# ethernet.net
KiCad netlist of a schematic drawn in Altium Designer
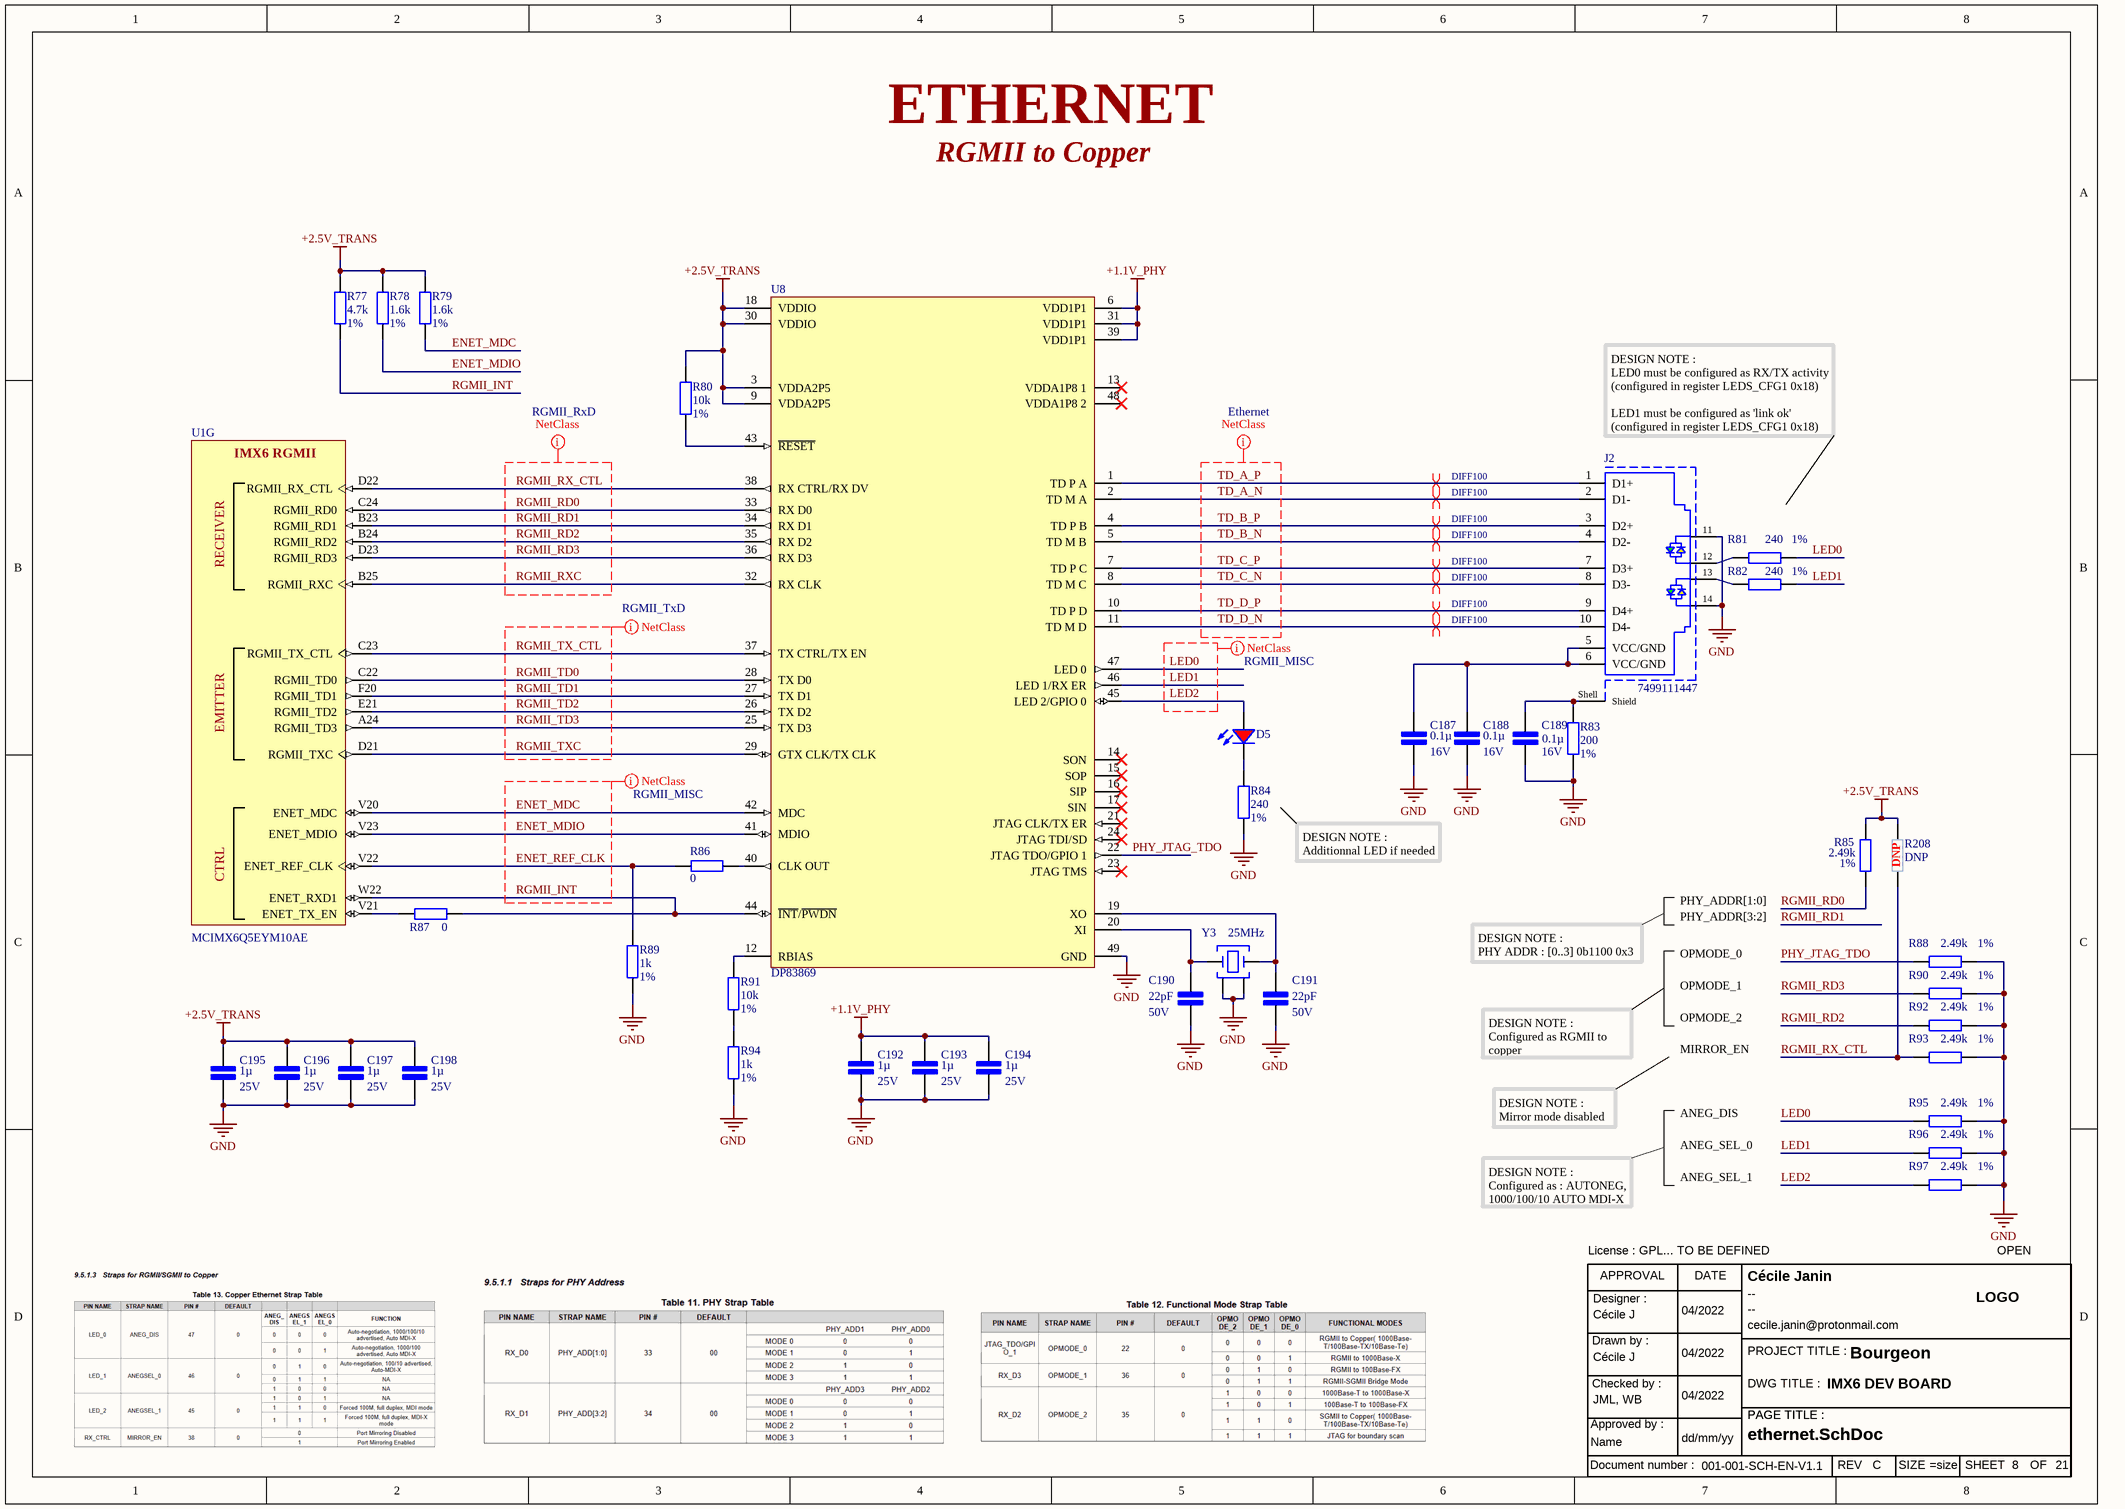
[diagram p0: ethernet.SchDoc]

(export (version "E")
  (design (tool "Eeschema 10.0.6"))
  (components
    (comp (ref "C187")
      (value "0.1µ")
      (footprint "Cap cer 0402/1005")
      (description "cap solid electrolyte 0.1µ 6.3V 10%")
      (fields (field (name "TENSION DU DIÉLECTRIQUE") "16V"))
      (libsource (lib "First Board IMX6") (part "cap 0.1µ 16V"))
    )
    (comp (ref "C188")
      (value "0.1µ")
      (footprint "Cap cer 0402/1005")
      (description "cap solid electrolyte 0.1µ 6.3V 10%")
      (fields (field (name "TENSION DU DIÉLECTRIQUE") "16V"))
      (libsource (lib "First Board IMX6") (part "cap 0.1µ 16V"))
    )
    (comp (ref "C189")
      (value "0.1µ")
      (footprint "Cap cer 0402/1005")
      (description "cap solid electrolyte 0.1µ 6.3V 10%")
      (fields (field (name "TENSION DU DIÉLECTRIQUE") "16V"))
      (libsource (lib "") (part "cap 0.1µ 16V_1"))
    )
    (comp (ref "C190")
      (value "22pF")
      (footprint "Cap cer 0402/1005")
      (description "cap cer 22pF 50V 5% NP0 0402")
      (fields (field (name "TENSION DU DIÉLECTRIQUE") "50V"))
      (libsource (lib "First Board IMX6") (part "cap 22pF 50V"))
    )
    (comp (ref "C191")
      (value "22pF")
      (footprint "Cap cer 0402/1005")
      (description "cap cer 22pF 50V 5% NP0 0402")
      (fields (field (name "TENSION DU DIÉLECTRIQUE") "50V"))
      (libsource (lib "First Board IMX6") (part "cap 22pF 50V"))
    )
    (comp (ref "C192")
      (value "1µ")
      (footprint "Cap cer 0402/1005")
      (description "cap cer 1µ 25V 10% X5R 0402")
      (fields (field (name "TENSION DU DIÉLECTRIQUE") "25V"))
      (libsource (lib "First Board IMX6") (part "cap 1µ 25V"))
    )
    (comp (ref "C193")
      (value "1µ")
      (footprint "Cap cer 0402/1005")
      (description "cap cer 1µ 25V 10% X5R 0402")
      (fields (field (name "TENSION DU DIÉLECTRIQUE") "25V"))
      (libsource (lib "First Board IMX6") (part "cap 1µ 25V"))
    )
    (comp (ref "C194")
      (value "1µ")
      (footprint "Cap cer 0402/1005")
      (description "cap cer 1µ 25V 10% X5R 0402")
      (fields (field (name "TENSION DU DIÉLECTRIQUE") "25V"))
      (libsource (lib "First Board IMX6") (part "cap 1µ 25V"))
    )
    (comp (ref "C195")
      (value "1µ")
      (footprint "Cap cer 0402/1005")
      (description "cap cer 1µ 25V 10% X5R 0402")
      (fields (field (name "TENSION DU DIÉLECTRIQUE") "25V"))
      (libsource (lib "First Board IMX6") (part "cap 1µ 25V"))
    )
    (comp (ref "C196")
      (value "1µ")
      (footprint "Cap cer 0402/1005")
      (description "cap cer 1µ 25V 10% X5R 0402")
      (fields (field (name "TENSION DU DIÉLECTRIQUE") "25V"))
      (libsource (lib "First Board IMX6") (part "cap 1µ 25V"))
    )
    (comp (ref "C197")
      (value "1µ")
      (footprint "Cap cer 0402/1005")
      (description "cap cer 1µ 25V 10% X5R 0402")
      (fields (field (name "TENSION DU DIÉLECTRIQUE") "25V"))
      (libsource (lib "First Board IMX6") (part "cap 1µ 25V"))
    )
    (comp (ref "C198")
      (value "1µ")
      (footprint "Cap cer 0402/1005")
      (description "cap cer 1µ 25V 10% X5R 0402")
      (fields (field (name "TENSION DU DIÉLECTRIQUE") "25V"))
      (libsource (lib "First Board IMX6") (part "cap 1µ 25V"))
    )
    (comp (ref "D5")
      (value "Red, 2V, 120deg")
      (footprint "LED red 0603")
      (description "WL-SMCC SMD Mono-color Chip LED Compact, size 0603, Red, 2V, 120deg 150060RS73220")
      (fields (field (name "PART NUMBER") "150060RS73220") (field (name "PUBLISHER") "Wurth Elektronik"))
      (libsource (lib "First Board IMX6") (part "LED Red 0603"))
    )
    (comp (ref "J2")
      (value "7499111447")
      (footprint "RJ45 7499111447")
      (libsource (lib "First Board IMX6") (part "RJ45 7499111447"))
    )
    (comp (ref "R77")
      (value "4.7k")
      (footprint "Res 0402/1005")
      (description "res 4.7k 1% 0402")
      (fields (field (name "POURCENTAGE") "1%"))
      (libsource (lib "First Board IMX6") (part "res 4.7k 1%"))
    )
    (comp (ref "R78")
      (value "1.6k")
      (footprint "Res 0402/1005")
      (description "res 1.6k 1% 0402")
      (fields (field (name "POURCENTAGE") "1%"))
      (libsource (lib "First Board IMX6") (part "res 1.6k 1%"))
    )
    (comp (ref "R79")
      (value "1.6k")
      (footprint "Res 0402/1005")
      (description "res 1.6k 1% 0402")
      (fields (field (name "POURCENTAGE") "1%"))
      (libsource (lib "First Board IMX6") (part "res 1.6k 1%"))
    )
    (comp (ref "R80")
      (value "10k")
      (footprint "Res 0402/1005")
      (description "res 10k 1% 0402")
      (fields (field (name "POURCENTAGE") "1%"))
      (libsource (lib "First Board IMX6") (part "res 10k 1%"))
    )
    (comp (ref "R81")
      (value "240")
      (footprint "Res 0402/1005")
      (description "res 240 1% 0402")
      (fields (field (name "POURCENTAGE") "1%"))
      (libsource (lib "First Board IMX6") (part "res 240 1%"))
    )
    (comp (ref "R82")
      (value "240")
      (footprint "Res 0402/1005")
      (description "res 240 1% 0402")
      (fields (field (name "POURCENTAGE") "1%"))
      (libsource (lib "First Board IMX6") (part "res 240 1%"))
    )
    (comp (ref "R83")
      (value "200")
      (footprint "Res 0402/1005")
      (description "res 200 1% 0402")
      (fields (field (name "POURCENTAGE") "1%"))
      (libsource (lib "First Board IMX6") (part "res 200 1%"))
    )
    (comp (ref "R84")
      (value "240")
      (footprint "Res 0402/1005")
      (description "res 240 1% 0402")
      (fields (field (name "POURCENTAGE") "1%"))
      (libsource (lib "First Board IMX6") (part "res 240 1%"))
    )
    (comp (ref "R85")
      (value "2.49k")
      (footprint "Res 0402/1005")
      (description "res 2.49k 1% 0402")
      (fields (field (name "POURCENTAGE") "1%"))
      (libsource (lib "First Board IMX6") (part "res 2.49k 1%"))
    )
    (comp (ref "R86")
      (value "0")
      (footprint "Res 0402/1005")
      (description "res 0402")
      (libsource (lib "First Board IMX6") (part "res 0Ohm small"))
    )
    (comp (ref "R87")
      (value "0")
      (footprint "Res 0402/1005")
      (description "res 0402")
      (libsource (lib "First Board IMX6") (part "res 0Ohm small"))
    )
    (comp (ref "R88")
      (value "2.49k")
      (footprint "Res 0402/1005")
      (description "res 2.49k 1% 0402")
      (fields (field (name "POURCENTAGE") "1%"))
      (libsource (lib "First Board IMX6") (part "res 2.49k 1%"))
    )
    (comp (ref "R89")
      (value "1k")
      (footprint "Res 0402/1005")
      (description "res 1k 1% 0402")
      (fields (field (name "POURCENTAGE") "1%"))
      (libsource (lib "First Board IMX6") (part "res 1k 1%"))
    )
    (comp (ref "R90")
      (value "2.49k")
      (footprint "Res 0402/1005")
      (description "res 2.49k 1% 0402")
      (fields (field (name "POURCENTAGE") "1%"))
      (libsource (lib "First Board IMX6") (part "res 2.49k 1%"))
    )
    (comp (ref "R91")
      (value "10k")
      (footprint "Res 0402/1005")
      (description "res 10k 1% 0402")
      (fields (field (name "POURCENTAGE") "1%"))
      (libsource (lib "First Board IMX6") (part "res 10k 1%"))
    )
    (comp (ref "R92")
      (value "2.49k")
      (footprint "Res 0402/1005")
      (description "res 2.49k 1% 0402")
      (fields (field (name "POURCENTAGE") "1%"))
      (libsource (lib "First Board IMX6") (part "res 2.49k 1%"))
    )
    (comp (ref "R93")
      (value "2.49k")
      (footprint "Res 0402/1005")
      (description "res 2.49k 1% 0402")
      (fields (field (name "POURCENTAGE") "1%"))
      (libsource (lib "First Board IMX6") (part "res 2.49k 1%"))
    )
    (comp (ref "R94")
      (value "1k")
      (footprint "Res 0402/1005")
      (description "res 1k 1% 0402")
      (fields (field (name "POURCENTAGE") "1%"))
      (libsource (lib "First Board IMX6") (part "res 1k 1%"))
    )
    (comp (ref "R95")
      (value "2.49k")
      (footprint "Res 0402/1005")
      (description "res 2.49k 1% 0402")
      (fields (field (name "POURCENTAGE") "1%"))
      (libsource (lib "First Board IMX6") (part "res 2.49k 1%"))
    )
    (comp (ref "R96")
      (value "2.49k")
      (footprint "Res 0402/1005")
      (description "res 2.49k 1% 0402")
      (fields (field (name "POURCENTAGE") "1%"))
      (libsource (lib "First Board IMX6") (part "res 2.49k 1%"))
    )
    (comp (ref "R97")
      (value "2.49k")
      (footprint "Res 0402/1005")
      (description "res 2.49k 1% 0402")
      (fields (field (name "POURCENTAGE") "1%"))
      (libsource (lib "First Board IMX6") (part "res 2.49k 1%"))
    )
    (comp (ref "R208")
      (value "DNP")
      (footprint "Res 0402/1005")
      (description "res DNP 0403")
      (libsource (lib "First Board IMX6") (part "res DNP 0402"))
    )
    (comp (ref "TB7")
      (value "Title bloc ANSI modified")
      (libsource (lib "First Board IMX6") (part "Title bloc ANSI"))
    )
    (comp (ref "U1")
      (value "MCIMX6Q5EYM10AE")
      (footprint "FRES-2197-01")
      (fields
        (field (name "PARTNUMBER") "MCIMX6Q5EYM10ACR")
        (field (name "MANUFACTURER") "Freescale Semiconductor")
      )
      (libsource (lib "First Board IMX6") (part "IMX6Q5EYM10AE"))
    )
    (comp (ref "U8")
      (value "DP83869")
      (footprint "QFN48")
      (description "Ethernet transciever")
      (libsource (lib "First Board IMX6") (part "IC DP83869"))
    )
    (comp (ref "Y3")
      (value "25MHz")
      (footprint "IQXC-42")
      (description "WE-XTAL, 25MHz, +/-10ppm")
      (fields
        (field (name "MANUFACTURER PART NUMBER") "830108212509")
        (field (name "MANUFACTURER") "Wurth Elektronik")
      )
      (libsource (lib "First Board IMX6") (part "XTAL 25MHz"))
    )
  )
  (nets
    (net (code "1") (name "+1.1V_PHY") (class "Default")
      (node (ref "C192") (pin "1") (pinfunction "3_1") (pintype "passive"))
      (node (ref "C193") (pin "1") (pinfunction "3_1") (pintype "passive"))
      (node (ref "C194") (pin "1") (pinfunction "3_1") (pintype "passive"))
      (node (ref "U8") (pin "31") (pinfunction "VDD1P1_31") (pintype "power_in"))
      (node (ref "U8") (pin "39") (pinfunction "VDD1P1_39") (pintype "power_in"))
      (node (ref "U8") (pin "6") (pinfunction "VDD1P1_6") (pintype "power_in"))
    )
    (net (code "2") (name "+2.5V_TRANS") (class "Default")
      (node (ref "C195") (pin "1") (pinfunction "3_1") (pintype "passive"))
      (node (ref "C196") (pin "1") (pinfunction "3_1") (pintype "passive"))
      (node (ref "C197") (pin "1") (pinfunction "3_1") (pintype "passive"))
      (node (ref "C198") (pin "1") (pinfunction "3_1") (pintype "passive"))
      (node (ref "R208") (pin "2") (pintype "passive"))
      (node (ref "R77") (pin "2") (pintype "passive"))
      (node (ref "R78") (pin "2") (pintype "passive"))
      (node (ref "R79") (pin "2") (pintype "passive"))
      (node (ref "R80") (pin "2") (pintype "passive"))
      (node (ref "R85") (pin "2") (pintype "passive"))
      (node (ref "U8") (pin "18") (pinfunction "VDDIO_18") (pintype "power_in"))
      (node (ref "U8") (pin "3") (pinfunction "VDDA2P5_3") (pintype "power_in"))
      (node (ref "U8") (pin "30") (pinfunction "VDDIO_30") (pintype "power_in"))
      (node (ref "U8") (pin "9") (pinfunction "VDDA2P5_9") (pintype "power_in"))
    )
    (net (code "3") (name "/ENET_MDC") (class "Default")
      (node (ref "R79") (pin "1") (pintype "passive"))
      (node (ref "U1") (pin "V20") (pinfunction "ENET_MDC_V20") (pintype "bidirectional"))
      (node (ref "U8") (pin "42") (pinfunction "MDC_42") (pintype "input"))
    )
    (net (code "4") (name "/ENET_MDIO") (class "Default")
      (node (ref "R78") (pin "1") (pintype "passive"))
      (node (ref "U1") (pin "V23") (pinfunction "ENET_MDIO_V23") (pintype "bidirectional"))
      (node (ref "U8") (pin "41") (pinfunction "MDIO_41") (pintype "bidirectional"))
    )
    (net (code "5") (name "/ENET_REF_CLK") (class "Default")
      (node (ref "R86") (pin "1") (pintype "passive"))
      (node (ref "R89") (pin "2") (pintype "passive"))
      (node (ref "U1") (pin "V22") (pinfunction "ENET_REF_CLK_V22") (pintype "bidirectional"))
    )
    (net (code "6") (name "/LED0") (class "Default")
      (node (ref "R81") (pin "2") (pintype "passive"))
      (node (ref "R95") (pin "2") (pintype "passive"))
      (node (ref "U8") (pin "47") (pinfunction "LED_0_47") (pintype "output"))
    )
    (net (code "7") (name "/LED1") (class "Default")
      (node (ref "R82") (pin "2") (pintype "passive"))
      (node (ref "R96") (pin "2") (pintype "passive"))
      (node (ref "U8") (pin "46") (pinfunction "LED_1/RX_ER_46") (pintype "output"))
    )
    (net (code "8") (name "/LED2") (class "Default")
      (node (ref "D5") (pin "2") (pinfunction "A_2") (pintype "passive"))
      (node (ref "R97") (pin "2") (pintype "passive"))
      (node (ref "U8") (pin "45") (pinfunction "LED_2/GPIO_0_45") (pintype "bidirectional"))
    )
    (net (code "9") (name "/PHY_JTAG_TDO") (class "Default")
      (node (ref "R88") (pin "2") (pintype "passive"))
      (node (ref "U8") (pin "22") (pinfunction "JTAG_TDO/GPIO_1_22") (pintype "output"))
    )
    (net (code "10") (name "/RGMII_INT") (class "Default")
      (node (ref "R77") (pin "1") (pintype "passive"))
      (node (ref "R87") (pin "2") (pintype "passive"))
      (node (ref "U1") (pin "W22") (pinfunction "ENET_RXD1_W22") (pintype "bidirectional"))
      (node (ref "U8") (pin "44") (pinfunction "~{INT}/~{PWDN}_44") (pintype "bidirectional"))
    )
    (net (code "11") (name "/RGMII_RD0") (class "Default")
      (node (ref "R85") (pin "1") (pintype "passive"))
      (node (ref "U1") (pin "C24") (pinfunction "RGMII_RD0_C24") (pintype "input"))
      (node (ref "U8") (pin "33") (pinfunction "RX_D0_33") (pintype "output"))
    )
    (net (code "12") (name "/RGMII_RD1") (class "Default")
      (node (ref "U1") (pin "B23") (pinfunction "RGMII_RD1_B23") (pintype "input"))
      (node (ref "U8") (pin "34") (pinfunction "RX_D1_34") (pintype "output"))
    )
    (net (code "13") (name "/RGMII_RD2") (class "Default")
      (node (ref "R92") (pin "2") (pintype "passive"))
      (node (ref "U1") (pin "B24") (pinfunction "RGMII_RD2_B24") (pintype "input"))
      (node (ref "U8") (pin "35") (pinfunction "RX_D2_35") (pintype "output"))
    )
    (net (code "14") (name "/RGMII_RD3") (class "Default")
      (node (ref "R90") (pin "2") (pintype "passive"))
      (node (ref "U1") (pin "D23") (pinfunction "RGMII_RD3_D23") (pintype "input"))
      (node (ref "U8") (pin "36") (pinfunction "RX_D3_36") (pintype "output"))
    )
    (net (code "15") (name "/RGMII_RXC") (class "Default")
      (node (ref "U1") (pin "B25") (pinfunction "RGMII_RXC_B25") (pintype "input"))
      (node (ref "U8") (pin "32") (pinfunction "RX_CLK_32") (pintype "output"))
    )
    (net (code "16") (name "/RGMII_RX_CTL") (class "Default")
      (node (ref "R208") (pin "1") (pintype "passive"))
      (node (ref "R93") (pin "2") (pintype "passive"))
      (node (ref "U1") (pin "D22") (pinfunction "RGMII_RX_CTL_D22") (pintype "input"))
      (node (ref "U8") (pin "38") (pinfunction "RX_CTRL/RX_DV_38") (pintype "output"))
    )
    (net (code "17") (name "/RGMII_TD0") (class "Default")
      (node (ref "U1") (pin "C22") (pinfunction "RGMII_TD0_C22") (pintype "output"))
      (node (ref "U8") (pin "28") (pinfunction "TX_D0_28") (pintype "input"))
    )
    (net (code "18") (name "/RGMII_TD1") (class "Default")
      (node (ref "U1") (pin "F20") (pinfunction "RGMII_TD1_F20") (pintype "output"))
      (node (ref "U8") (pin "27") (pinfunction "TX_D1_27") (pintype "input"))
    )
    (net (code "19") (name "/RGMII_TD2") (class "Default")
      (node (ref "U1") (pin "E21") (pinfunction "RGMII_TD2_E21") (pintype "output"))
      (node (ref "U8") (pin "26") (pinfunction "TX_D2_26") (pintype "input"))
    )
    (net (code "20") (name "/RGMII_TD3") (class "Default")
      (node (ref "U1") (pin "A24") (pinfunction "RGMII_TD3_A24") (pintype "output"))
      (node (ref "U8") (pin "25") (pinfunction "TX_D3_25") (pintype "input"))
    )
    (net (code "21") (name "/RGMII_TXC") (class "Default")
      (node (ref "U1") (pin "D21") (pinfunction "RGMII_TXC_D21") (pintype "output"))
      (node (ref "U8") (pin "29") (pinfunction "GTX_CLK/TX_CLK_29") (pintype "bidirectional"))
    )
    (net (code "22") (name "/RGMII_TX_CTL") (class "Default")
      (node (ref "U1") (pin "C23") (pinfunction "RGMII_TX_CTL_C23") (pintype "output"))
      (node (ref "U8") (pin "37") (pinfunction "TX_CTRL/TX_EN_37") (pintype "input"))
    )
    (net (code "23") (name "/TD_A_N") (class "Default")
      (node (ref "J2") (pin "2") (pinfunction "D1-_2") (pintype "passive"))
      (node (ref "U8") (pin "2") (pinfunction "TD_M_A_2") (pintype "passive"))
    )
    (net (code "24") (name "/TD_A_P") (class "Default")
      (node (ref "J2") (pin "1") (pinfunction "D1+_1") (pintype "passive"))
      (node (ref "U8") (pin "1") (pinfunction "TD_P_A_1") (pintype "passive"))
    )
    (net (code "25") (name "/TD_B_N") (class "Default")
      (node (ref "J2") (pin "4") (pinfunction "D2-_4") (pintype "passive"))
      (node (ref "U8") (pin "5") (pinfunction "TD_M_B_5") (pintype "passive"))
    )
    (net (code "26") (name "/TD_B_P") (class "Default")
      (node (ref "J2") (pin "3") (pinfunction "D2+_3") (pintype "passive"))
      (node (ref "U8") (pin "4") (pinfunction "TD_P_B_4") (pintype "passive"))
    )
    (net (code "27") (name "/TD_C_N") (class "Default")
      (node (ref "J2") (pin "8") (pinfunction "D3-_8") (pintype "passive"))
      (node (ref "U8") (pin "8") (pinfunction "TD_M_C_8") (pintype "passive"))
    )
    (net (code "28") (name "/TD_C_P") (class "Default")
      (node (ref "J2") (pin "7") (pinfunction "D3+_7") (pintype "passive"))
      (node (ref "U8") (pin "7") (pinfunction "TD_P_C_7") (pintype "passive"))
    )
    (net (code "29") (name "/TD_D_N") (class "Default")
      (node (ref "J2") (pin "10") (pinfunction "D4-_10") (pintype "passive"))
      (node (ref "U8") (pin "11") (pinfunction "TD_M_D_11") (pintype "passive"))
    )
    (net (code "30") (name "/TD_D_P") (class "Default")
      (node (ref "J2") (pin "9") (pinfunction "D4+_9") (pintype "passive"))
      (node (ref "U8") (pin "10") (pinfunction "TD_P_D_10") (pintype "passive"))
    )
    (net (code "31") (name "GND") (class "Default")
      (node (ref "C187") (pin "2") (pinfunction "4_2") (pintype "passive"))
      (node (ref "C188") (pin "2") (pinfunction "4_2") (pintype "passive"))
      (node (ref "C189") (pin "2") (pinfunction "4_2") (pintype "passive"))
      (node (ref "C190") (pin "2") (pinfunction "4_2") (pintype "passive"))
      (node (ref "C191") (pin "2") (pinfunction "4_2") (pintype "passive"))
      (node (ref "C192") (pin "2") (pinfunction "4_2") (pintype "passive"))
      (node (ref "C193") (pin "2") (pinfunction "4_2") (pintype "passive"))
      (node (ref "C194") (pin "2") (pinfunction "4_2") (pintype "passive"))
      (node (ref "C195") (pin "2") (pinfunction "4_2") (pintype "passive"))
      (node (ref "C196") (pin "2") (pinfunction "4_2") (pintype "passive"))
      (node (ref "C197") (pin "2") (pinfunction "4_2") (pintype "passive"))
      (node (ref "C198") (pin "2") (pinfunction "4_2") (pintype "passive"))
      (node (ref "J2") (pin "11") (pinfunction "11_11") (pintype "passive"))
      (node (ref "J2") (pin "14") (pinfunction "14_14") (pintype "passive"))
      (node (ref "R83") (pin "1") (pintype "passive"))
      (node (ref "R84") (pin "1") (pintype "passive"))
      (node (ref "R88") (pin "1") (pintype "passive"))
      (node (ref "R89") (pin "1") (pintype "passive"))
      (node (ref "R90") (pin "1") (pintype "passive"))
      (node (ref "R92") (pin "1") (pintype "passive"))
      (node (ref "R93") (pin "1") (pintype "passive"))
      (node (ref "R94") (pin "1") (pintype "passive"))
      (node (ref "R95") (pin "1") (pintype "passive"))
      (node (ref "R96") (pin "1") (pintype "passive"))
      (node (ref "R97") (pin "1") (pintype "passive"))
      (node (ref "U8") (pin "49") (pinfunction "GND_49") (pintype "power_in"))
      (node (ref "Y3") (pin "2") (pinfunction "GND_2") (pintype "passive"))
      (node (ref "Y3") (pin "4") (pinfunction "GND_4") (pintype "passive"))
    )
    (net (code "32") (name "Net-(C187-3)") (class "Default")
      (node (ref "C187") (pin "1") (pinfunction "3_1") (pintype "passive"))
      (node (ref "C188") (pin "1") (pinfunction "3_1") (pintype "passive"))
      (node (ref "J2") (pin "5") (pinfunction "VCC/GND_5") (pintype "passive"))
      (node (ref "J2") (pin "6") (pinfunction "VCC/GND_6") (pintype "passive"))
    )
    (net (code "33") (name "Net-(C189-3)") (class "Default")
      (node (ref "C189") (pin "1") (pinfunction "3_1") (pintype "passive"))
      (node (ref "J2") (pin "Shell") (pinfunction "Shield_Shell") (pintype "passive"))
      (node (ref "R83") (pin "2") (pintype "passive"))
    )
    (net (code "34") (name "Net-(C190-3)") (class "Default")
      (node (ref "C190") (pin "1") (pinfunction "3_1") (pintype "passive"))
      (node (ref "U8") (pin "20") (pinfunction "XI_20") (pintype "passive"))
      (node (ref "Y3") (pin "1") (pinfunction "Crystal_1") (pintype "passive"))
    )
    (net (code "35") (name "Net-(C191-3)") (class "Default")
      (node (ref "C191") (pin "1") (pinfunction "3_1") (pintype "passive"))
      (node (ref "U8") (pin "19") (pinfunction "XO_19") (pintype "passive"))
      (node (ref "Y3") (pin "3") (pinfunction "Crystal_3") (pintype "passive"))
    )
    (net (code "36") (name "Net-(D5-K)") (class "Default")
      (node (ref "D5") (pin "1") (pinfunction "K_1") (pintype "passive"))
      (node (ref "R84") (pin "2") (pintype "passive"))
    )
    (net (code "37") (name "Net-(J2-Pad12)") (class "Default")
      (node (ref "J2") (pin "12") (pinfunction "12_12") (pintype "passive"))
      (node (ref "R81") (pin "1") (pintype "passive"))
    )
    (net (code "38") (name "Net-(J2-Pad13)") (class "Default")
      (node (ref "J2") (pin "13") (pinfunction "13_13") (pintype "passive"))
      (node (ref "R82") (pin "1") (pintype "passive"))
    )
    (net (code "39") (name "Net-(R91-Pad1)") (class "Default")
      (node (ref "R91") (pin "1") (pintype "passive"))
      (node (ref "R94") (pin "2") (pintype "passive"))
    )
    (net (code "40") (name "Net-(U1G-ENET_TX_EN)") (class "Default")
      (node (ref "R87") (pin "1") (pintype "passive"))
      (node (ref "U1") (pin "V21") (pinfunction "ENET_TX_EN_V21") (pintype "bidirectional"))
    )
    (net (code "41") (name "Net-(U8-CLK_OUT)") (class "Default")
      (node (ref "R86") (pin "2") (pintype "passive"))
      (node (ref "U8") (pin "40") (pinfunction "CLK_OUT_40") (pintype "output"))
    )
    (net (code "42") (name "Net-(U8-RBIAS)") (class "Default")
      (node (ref "R91") (pin "2") (pintype "passive"))
      (node (ref "U8") (pin "12") (pinfunction "RBIAS_12") (pintype "passive"))
    )
    (net (code "43") (name "Net-(U8-~{RESET})") (class "Default")
      (node (ref "R80") (pin "1") (pintype "passive"))
      (node (ref "U8") (pin "43") (pinfunction "~{RESET}_43") (pintype "input"))
    )
    (net (code "44") (name "unconnected-(U8-JTAG_CLK{slash}TX_ER-Pad21)") (class "Default")
      (node (ref "U8") (pin "21") (pinfunction "JTAG_CLK/TX_ER_21") (pintype "input+no_connect"))
    )
    (net (code "45") (name "unconnected-(U8-JTAG_TDI{slash}SD-Pad24)") (class "Default")
      (node (ref "U8") (pin "24") (pinfunction "JTAG_TDI/SD_24") (pintype "input+no_connect"))
    )
    (net (code "46") (name "unconnected-(U8-JTAG_TMS-Pad23)") (class "Default")
      (node (ref "U8") (pin "23") (pinfunction "JTAG_TMS_23") (pintype "input+no_connect"))
    )
    (net (code "47") (name "unconnected-(U8-SIN-Pad17)") (class "Default")
      (node (ref "U8") (pin "17") (pinfunction "SIN_17") (pintype "passive+no_connect"))
    )
    (net (code "48") (name "unconnected-(U8-SIP-Pad16)") (class "Default")
      (node (ref "U8") (pin "16") (pinfunction "SIP_16") (pintype "passive+no_connect"))
    )
    (net (code "49") (name "unconnected-(U8-SON-Pad14)") (class "Default")
      (node (ref "U8") (pin "14") (pinfunction "SON_14") (pintype "passive+no_connect"))
    )
    (net (code "50") (name "unconnected-(U8-SOP-Pad15)") (class "Default")
      (node (ref "U8") (pin "15") (pinfunction "SOP_15") (pintype "passive+no_connect"))
    )
    (net (code "51") (name "unconnected-(U8-VDDA1P8_1-Pad13)") (class "Default")
      (node (ref "U8") (pin "13") (pinfunction "VDDA1P8_1_13") (pintype "power_in+no_connect"))
    )
    (net (code "52") (name "unconnected-(U8-VDDA1P8_2-Pad48)") (class "Default")
      (node (ref "U8") (pin "48") (pinfunction "VDDA1P8_2_48") (pintype "power_in+no_connect"))
    )
  )
)
